# ESP12.net
KiCad netlist of a schematic drawn in Altium Designer
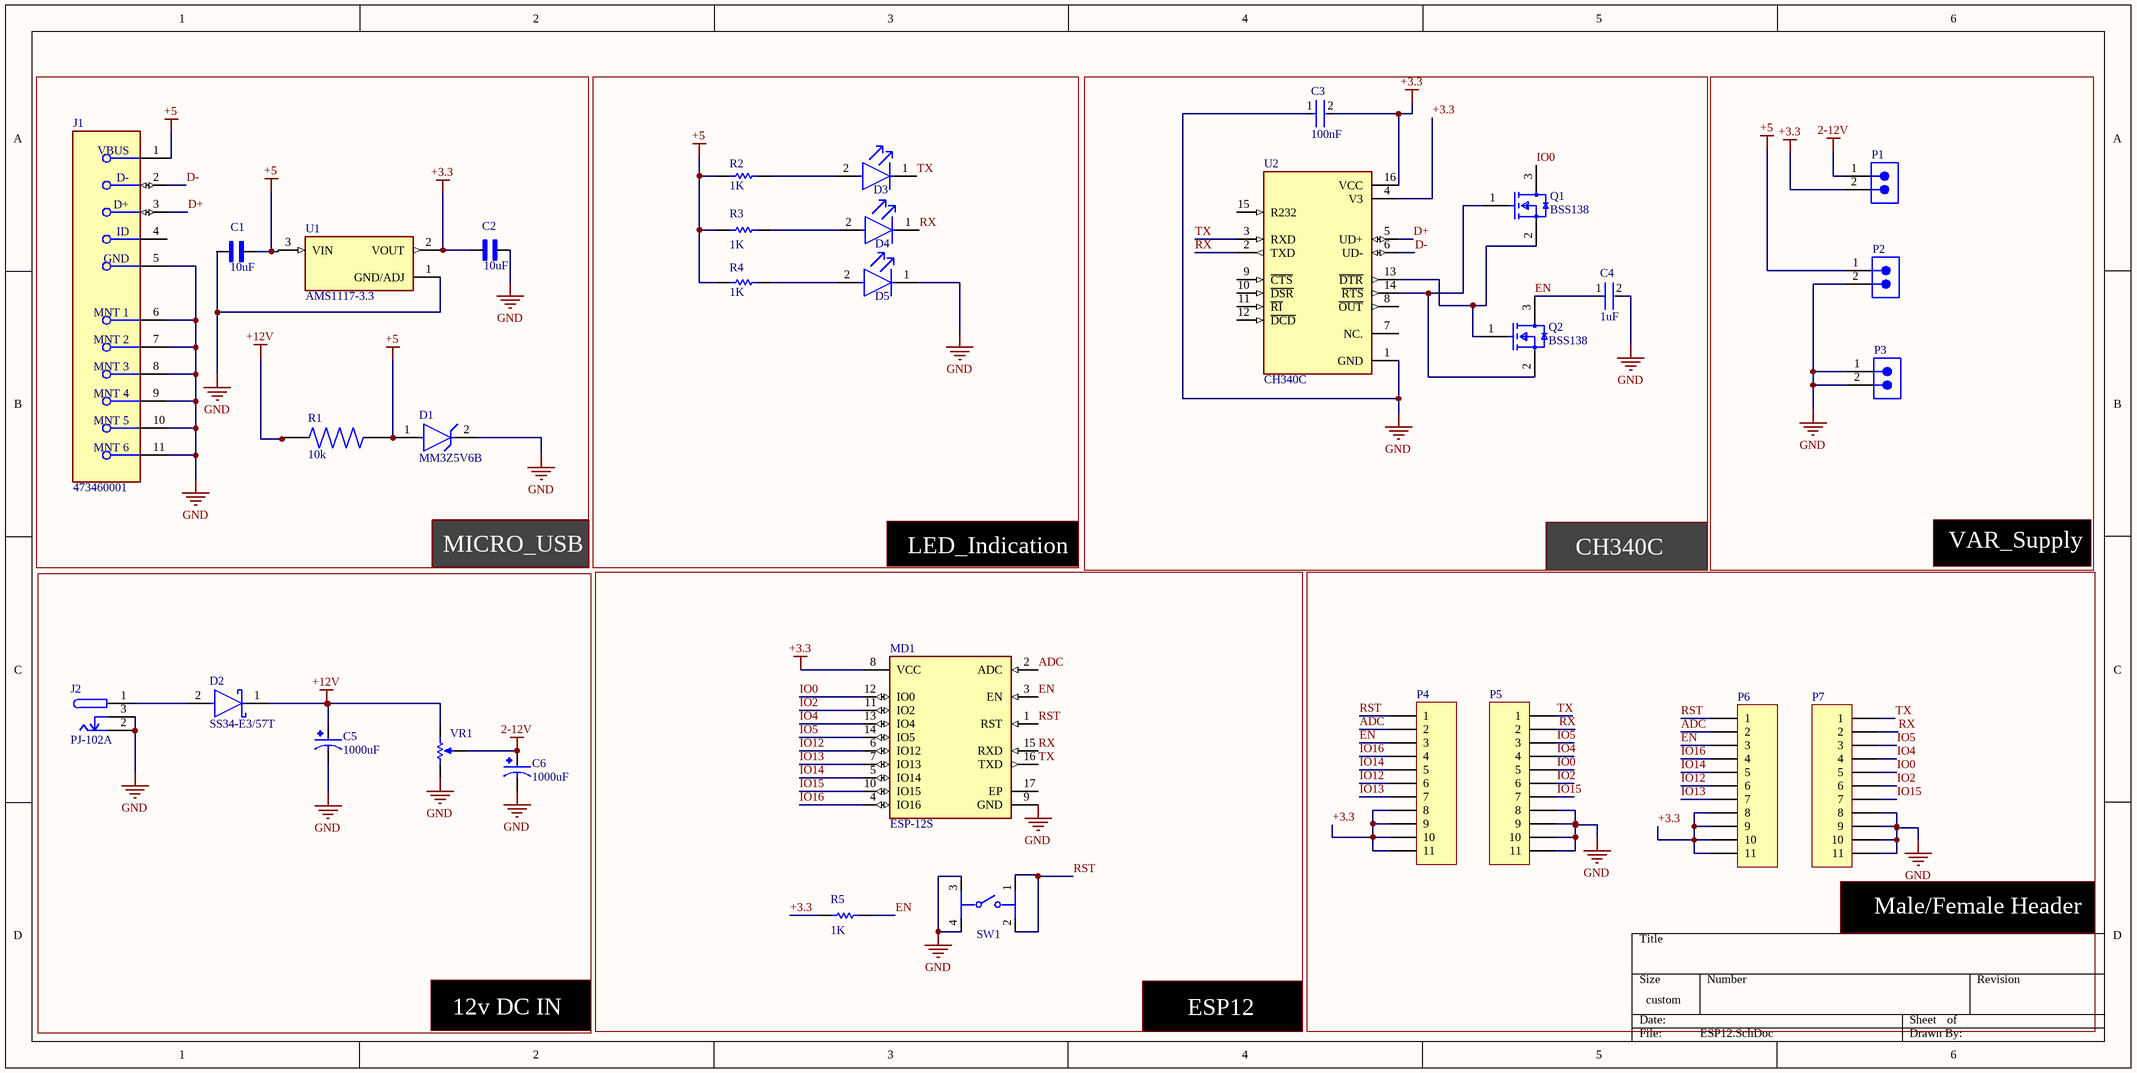
[diagram p0: ESP12.SchDoc]

(export (version "E")
  (design (tool "Eeschema 10.0.6"))
  (components
    (comp (ref "C1")
      (value "10uF")
      (footprint "CAPC2012X145N")
      (description "10 ÂµF Â±10% 25V Ceramic Capacitor X5R 0805 (2012 Metric)")
      (fields (field (name "MF") "Yageo") (field (name "MP") "CC0805KKX5R8BB106"))
      (libsource (lib "CC0805KKX5R8BB106") (part "CC0805KKX5R8BB106"))
    )
    (comp (ref "C2")
      (value "10uF")
      (footprint "CAPC2012X145N")
      (description "10 ÂµF Â±10% 25V Ceramic Capacitor X5R 0805 (2012 Metric)")
      (fields (field (name "MF") "Yageo") (field (name "MP") "CC0805KKX5R8BB106"))
      (libsource (lib "CC0805KKX5R8BB106") (part "CC0805KKX5R8BB106"))
    )
    (comp (ref "C3")
      (value "100nF")
      (footprint "FP-CC0805-0_85-MFG")
      (description "CAP CER 0.1UF 50V X7R 0805")
      (fields (field (name "TOLERANCE") "0.1") (field (name "MANUFACTURER PART NUMBER") "CC0805KRX7R9BB104"))
      (libsource (lib "Altium Content Vault") (part "11868f565c42a9108669ba33697ecf6"))
    )
    (comp (ref "C4")
      (value "1uF")
      (footprint "FP-CC0805-0_85-MFG")
      (description "CAP CER 1UF 16V X7R 0805")
      (fields
        (field (name "MANUFACTURER") "Yageo")
        (field (name "OCTOPART") "https://octopart.com/cc0805kkx7r7bb105-yageo-8376555")
      )
      (libsource (lib "Altium Content Vault") (part "11868f565c42a9108669ba33697ecf6"))
    )
    (comp (ref "C5")
      (value "1000uF")
      (footprint "CAPPRD500W60D1000H1600")
      (description "CAP ALUM 1000UF 20% 16V RADIAL")
      (fields (field (name "MF") "Panasonic") (field (name "MP") "EEU-FR1C102B"))
      (libsource (lib "EEUFR1C102B") (part "EEUFR1C102B"))
    )
    (comp (ref "C6")
      (value "1000uF")
      (footprint "CAPPRD500W60D1000H1600")
      (description "CAP ALUM 1000UF 20% 16V RADIAL")
      (fields (field (name "MF") "Panasonic") (field (name "MP") "EEU-FR1C102B"))
      (libsource (lib "EEUFR1C102B") (part "EEUFR1C102B"))
    )
    (comp (ref "D1")
      (value "MM3Z5V6B")
      (footprint "FP-MM3Z5V6B-MFG")
      (description "DIODE ZENER 5.6V 200MW SOD323F")
      (fields
        (field (name "MANUFACTURER") "ON Semiconductor")
        (field (name "OCTOPART") "https://octopart.com/mm3z5v6b-on+semiconductor-84329898")
      )
      (libsource (lib "Altium Content Vault") (part "3fba79ac723ca0a4e69928609483429"))
    )
    (comp (ref "D2")
      (value "SS34-E3/57T")
      (footprint "FP-95402-MFG")
      (description "DIODE SCHOTTKY 40V 3A DO214AB")
      (fields
        (field (name "MANUFACTURER") "Vishay")
        (field (name "OCTOPART") "https://octopart.com/ss34-e3%2F57t-vishay-39552907")
      )
      (libsource (lib "Altium Content Vault") (part "1d6ec82d83fb6aee721767c19dac4b9"))
    )
    (comp (ref "D3")
      (value "LTST-C190KRKT")
      (footprint "FP-LTST-C190KRKT-MFG")
      (description "LED RED CLEAR CHIP SMD")
      (libsource (lib "Altium Content Vault") (part "8706943c75ba83719d021d2fdc84c58"))
    )
    (comp (ref "D4")
      (value "LTST-C190KGKT")
      (footprint "FP-LTST-C190KGKT-MFG")
      (description "LED GREEN CLEAR CHIP SMD")
      (libsource (lib "Altium Content Vault") (part "8706943c75ba83719d021d2fdc84c58"))
    )
    (comp (ref "D5")
      (value "LTST-C190KRKT")
      (footprint "FP-LTST-C190KRKT-MFG")
      (description "LED RED CLEAR CHIP SMD")
      (libsource (lib "Altium Content Vault") (part "8706943c75ba83719d021d2fdc84c58"))
    )
    (comp (ref "J1")
      (value "473460001")
      (footprint "FP-473460001-MFG")
      (description "CONN RCPT USB2.0 MICRO B SMD R/A")
      (fields
        (field (name "OCTOPART") "https://octopart.com/47346-0001-molex-7164928")
        (field (name "MANUFACTURER") "Molex")
      )
      (libsource (lib "Altium Content Vault") (part "53ae1f1d9b557310b43ca686e5bb76a"))
    )
    (comp (ref "J2")
      (value "PJ-102A")
      (footprint "FP-PJ-102A-MFG")
      (description "PJ-102A 2.0 x 6.5 mm, 2.5 A, Horizontal, Through Hole, Tapered Pins, Dc Power Jack Connector")
      (libsource (lib "Altium Content Vault") (part "c639f672d24b5d70918fa8d934b95d1"))
    )
    (comp (ref "MD1")
      (value "ESP-12S")
      (footprint "FP-ESP-12S-MFG")
      (description "RX TXRX MOD WIFI PCB TRACE SMD")
      (libsource (lib "Altium Content Vault") (part "0473e498d6bc78f349d0f2898a8422c"))
    )
    (comp (ref "P1")
      (value "61300211121")
      (footprint "61300211121")
      (description "THT Vertical Pin Header WR-PHD, Pitch 2.54 mm, Single Row, 2 pins")
      (libsource (lib "Altium Content Vault") (part "Header_Male_1R_02P"))
    )
    (comp (ref "P2")
      (value "61300211121")
      (footprint "61300211121")
      (description "THT Vertical Pin Header WR-PHD, Pitch 2.54 mm, Single Row, 2 pins")
      (libsource (lib "Altium Content Vault") (part "Header_Male_1R_02P"))
    )
    (comp (ref "P3")
      (value "61300211121")
      (footprint "61300211121")
      (description "THT Vertical Pin Header WR-PHD, Pitch 2.54 mm, Single Row, 2 pins")
      (libsource (lib "Altium Content Vault") (part "Header_Male_1R_02P"))
    )
    (comp (ref "P4")
      (value "Header 11")
      (footprint "HDR1X11")
      (description "Header, 11-Pin")
      (fields (field (name "PUBLISHER") "Altium Limited"))
      (libsource (lib "") (part "Header 11_1"))
    )
    (comp (ref "P5")
      (value "Header 11")
      (footprint "HDR1X11")
      (description "Header, 11-Pin")
      (fields (field (name "PUBLISHER") "Altium Limited"))
      (libsource (lib "Miscellaneous Connectors") (part "Header 11"))
    )
    (comp (ref "P6")
      (value "Header 11")
      (footprint "HDR1X11")
      (description "Header, 11-Pin")
      (fields (field (name "PUBLISHER") "Altium Limited"))
      (libsource (lib "") (part "Header 11_1"))
    )
    (comp (ref "P7")
      (value "Header 11")
      (footprint "HDR1X11")
      (description "Header, 11-Pin")
      (fields (field (name "PUBLISHER") "Altium Limited"))
      (libsource (lib "Miscellaneous Connectors") (part "Header 11"))
    )
    (comp (ref "Q1")
      (value "BSS138")
      (footprint "FP-318-08-IPC_B")
      (description "MOSFET N-CH 50V 220MA SOT-23")
      (libsource (lib "Altium Content Vault") (part "3b9c635fedb024a5347a57b145af9cc"))
    )
    (comp (ref "Q2")
      (value "BSS138")
      (footprint "FP-318-08-IPC_B")
      (description "MOSFET N-CH 50V 220MA SOT-23")
      (libsource (lib "Altium Content Vault") (part "3b9c635fedb024a5347a57b145af9cc"))
    )
    (comp (ref "R1")
      (value "10k")
      (footprint "RESC2012X60N")
      (description "RESISTOR THICK FILM 5% 0.125W")
      (fields (field (name "MF") "{'manufacturer': u'YAGEO'}") (field (name "MP") "RC0805JR-0710KL"))
      (libsource (lib "RC0805JR-0710KL") (part "RC0805JR-0710KL"))
    )
    (comp (ref "R2")
      (value "1K")
      (footprint "RESC2013X60X35ML10T20")
      (description "Chip Resistor, 1 KOhm, +/- 1%, 125 mW, -55 to 155 degC, 0805 (2012 Metric), RoHS, Tape and Reel")
      (fields (field (name "TOLERANCE") "1%") (field (name "MANUFACTURER") "Yageo"))
      (libsource (lib "Altium Content Vault") (part "RES-2"))
    )
    (comp (ref "R3")
      (value "1K")
      (footprint "RESC2013X60X35ML10T20")
      (description "Chip Resistor, 1 KOhm, +/- 1%, 125 mW, -55 to 155 degC, 0805 (2012 Metric), RoHS, Tape and Reel")
      (fields (field (name "TOLERANCE") "1%") (field (name "MANUFACTURER") "Yageo"))
      (libsource (lib "Altium Content Vault") (part "RES-2"))
    )
    (comp (ref "R4")
      (value "1K")
      (footprint "RESC2013X60X35ML10T20")
      (description "Chip Resistor, 1 KOhm, +/- 1%, 125 mW, -55 to 155 degC, 0805 (2012 Metric), RoHS, Tape and Reel")
      (fields (field (name "TOLERANCE") "1%") (field (name "MANUFACTURER") "Yageo"))
      (libsource (lib "Altium Content Vault") (part "RES-2"))
    )
    (comp (ref "R5")
      (value "1K")
      (footprint "RESC2013X60X35ML10T20")
      (description "Chip Resistor, 1 KOhm, +/- 1%, 125 mW, -55 to 155 degC, 0805 (2012 Metric), RoHS, Tape and Reel")
      (fields (field (name "TOLERANCE") "1%") (field (name "MANUFACTURER") "Yageo"))
      (libsource (lib "Altium Content Vault") (part "RES-2"))
    )
    (comp (ref "SW1")
      (value "PTS645SM43SMTR92LFS")
      (footprint "PTS645SM43SMTR92LFS_MFG")
      (description "Switch Tactile N.O SPST Round Button Gull Wing 0.05A 12VDC 100000Cycle 1.57N SMD T/R")
      (libsource (lib "Altium Content Vault") (part "e4f2503661fe04264f50fb928c13ad2"))
    )
    (comp (ref "U1")
      (value "AMS1117-3.3")
      (footprint "SOT229P700X180-4N")
      (description "Sot223/Pkg 1-Amp 3.3-Volt Low Drop Out Voltage Regulatator")
      (fields (field (name "MF") "Advanced Monolithic Systems"))
      (libsource (lib "AMS1117-3.3") (part "AMS1117-3.3"))
    )
    (comp (ref "U2")
      (value "CH340C")
      (footprint "SOIC127P600X180-16N")
      (description "USB to serial chip CH340")
      (fields (field (name "MF") "WCH"))
      (libsource (lib "CH340C") (part "CH340C"))
    )
    (comp (ref "VR1")
      (value "3362P-1-103LF")
      (footprint "BOUR-3362P")
      (description "Square Trimpot(R) Trimming Potentiometer, 10 KOhm, 300 V, -55 to 125 degC, 3-Pin THD, RoHS, Tube")
      (fields (field (name "TOLERANCE") "1%"))
      (libsource (lib "Altium Content Vault") (part "RES-POT-3"))
    )
  )
  (nets
    (net (code "1") (name "+3.3") (class "Default")
      (node (ref "C2") (pin "1") (pinfunction "1_1") (pintype "passive"))
      (node (ref "C3") (pin "2") (pinfunction "2_2") (pintype "passive"))
      (node (ref "MD1") (pin "8") (pinfunction "VCC_8") (pintype "power_in"))
      (node (ref "P1") (pin "2") (pinfunction "2_2") (pintype "passive"))
      (node (ref "P4") (pin "10") (pinfunction "10_10") (pintype "passive"))
      (node (ref "P4") (pin "11") (pinfunction "11_11") (pintype "passive"))
      (node (ref "P4") (pin "8") (pinfunction "8_8") (pintype "passive"))
      (node (ref "P4") (pin "9") (pinfunction "9_9") (pintype "passive"))
      (node (ref "P6") (pin "10") (pinfunction "10_10") (pintype "passive"))
      (node (ref "P6") (pin "11") (pinfunction "11_11") (pintype "passive"))
      (node (ref "P6") (pin "8") (pinfunction "8_8") (pintype "passive"))
      (node (ref "P6") (pin "9") (pinfunction "9_9") (pintype "passive"))
      (node (ref "R5") (pin "1") (pinfunction "1_1") (pintype "passive"))
      (node (ref "U1") (pin "2") (pinfunction "VOUT_2") (pintype "output"))
      (node (ref "U2") (pin "16") (pinfunction "VCC_16") (pintype "power_in"))
      (node (ref "U2") (pin "4") (pinfunction "V3_4") (pintype "power_in"))
    )
    (net (code "2") (name "+5") (class "Default")
      (node (ref "C1") (pin "2") (pinfunction "2_2") (pintype "passive"))
      (node (ref "D1") (pin "1") (pinfunction "A_1") (pintype "passive"))
      (node (ref "J1") (pin "1") (pinfunction "VBUS_1") (pintype "power_in"))
      (node (ref "P2") (pin "1") (pinfunction "1_1") (pintype "passive"))
      (node (ref "R1") (pin "2") (pinfunction "2_2") (pintype "passive"))
      (node (ref "R2") (pin "1") (pinfunction "1_1") (pintype "passive"))
      (node (ref "R3") (pin "1") (pinfunction "1_1") (pintype "passive"))
      (node (ref "R4") (pin "1") (pinfunction "1_1") (pintype "passive"))
      (node (ref "U1") (pin "3") (pinfunction "VIN_3") (pintype "input"))
    )
    (net (code "3") (name "+12V") (class "Default")
      (node (ref "C5") (pin "P") (pinfunction "P_P") (pintype "passive"))
      (node (ref "D2") (pin "1") (pinfunction "C_1") (pintype "passive"))
      (node (ref "R1") (pin "1") (pinfunction "1_1") (pintype "passive"))
      (node (ref "VR1") (pin "3") (pinfunction "CW_3") (pintype "passive"))
    )
    (net (code "4") (name "/ADC") (class "Default")
      (node (ref "MD1") (pin "2") (pinfunction "ADC_2") (pintype "input"))
      (node (ref "P4") (pin "2") (pinfunction "2_2") (pintype "passive"))
      (node (ref "P6") (pin "2") (pinfunction "2_2") (pintype "passive"))
    )
    (net (code "5") (name "/D+") (class "Default")
      (node (ref "J1") (pin "3") (pinfunction "D+_3") (pintype "bidirectional"))
      (node (ref "U2") (pin "5") (pinfunction "UD+_5") (pintype "bidirectional"))
    )
    (net (code "6") (name "/D-") (class "Default")
      (node (ref "J1") (pin "2") (pinfunction "D-_2") (pintype "bidirectional"))
      (node (ref "U2") (pin "6") (pinfunction "UD-_6") (pintype "bidirectional"))
    )
    (net (code "7") (name "/EN") (class "Default")
      (node (ref "C4") (pin "1") (pinfunction "1_1") (pintype "passive"))
      (node (ref "MD1") (pin "3") (pinfunction "EN_3") (pintype "input"))
      (node (ref "P4") (pin "3") (pinfunction "3_3") (pintype "passive"))
      (node (ref "P6") (pin "3") (pinfunction "3_3") (pintype "passive"))
      (node (ref "Q2") (pin "3") (pinfunction "D_3") (pintype "passive"))
      (node (ref "R5") (pin "2") (pinfunction "2_2") (pintype "passive"))
    )
    (net (code "8") (name "/IO0") (class "Default")
      (node (ref "MD1") (pin "12") (pinfunction "IO0_12") (pintype "bidirectional"))
      (node (ref "P5") (pin "5") (pinfunction "5_5") (pintype "passive"))
      (node (ref "P7") (pin "5") (pinfunction "5_5") (pintype "passive"))
      (node (ref "Q1") (pin "3") (pinfunction "D_3") (pintype "passive"))
    )
    (net (code "9") (name "/IO2") (class "Default")
      (node (ref "MD1") (pin "11") (pinfunction "IO2_11") (pintype "bidirectional"))
      (node (ref "P5") (pin "6") (pinfunction "6_6") (pintype "passive"))
      (node (ref "P7") (pin "6") (pinfunction "6_6") (pintype "passive"))
    )
    (net (code "10") (name "/IO4") (class "Default")
      (node (ref "MD1") (pin "13") (pinfunction "IO4_13") (pintype "bidirectional"))
      (node (ref "P5") (pin "4") (pinfunction "4_4") (pintype "passive"))
      (node (ref "P7") (pin "4") (pinfunction "4_4") (pintype "passive"))
    )
    (net (code "11") (name "/IO5") (class "Default")
      (node (ref "MD1") (pin "14") (pinfunction "IO5_14") (pintype "bidirectional"))
      (node (ref "P5") (pin "3") (pinfunction "3_3") (pintype "passive"))
      (node (ref "P7") (pin "3") (pinfunction "3_3") (pintype "passive"))
    )
    (net (code "12") (name "/IO12") (class "Default")
      (node (ref "MD1") (pin "6") (pinfunction "IO12_6") (pintype "bidirectional"))
      (node (ref "P4") (pin "6") (pinfunction "6_6") (pintype "passive"))
      (node (ref "P6") (pin "6") (pinfunction "6_6") (pintype "passive"))
    )
    (net (code "13") (name "/IO13") (class "Default")
      (node (ref "MD1") (pin "7") (pinfunction "IO13_7") (pintype "bidirectional"))
      (node (ref "P4") (pin "7") (pinfunction "7_7") (pintype "passive"))
      (node (ref "P6") (pin "7") (pinfunction "7_7") (pintype "passive"))
    )
    (net (code "14") (name "/IO14") (class "Default")
      (node (ref "MD1") (pin "5") (pinfunction "IO14_5") (pintype "bidirectional"))
      (node (ref "P4") (pin "5") (pinfunction "5_5") (pintype "passive"))
      (node (ref "P6") (pin "5") (pinfunction "5_5") (pintype "passive"))
    )
    (net (code "15") (name "/IO15") (class "Default")
      (node (ref "MD1") (pin "10") (pinfunction "IO15_10") (pintype "bidirectional"))
      (node (ref "P5") (pin "7") (pinfunction "7_7") (pintype "passive"))
      (node (ref "P7") (pin "7") (pinfunction "7_7") (pintype "passive"))
    )
    (net (code "16") (name "/IO16") (class "Default")
      (node (ref "MD1") (pin "4") (pinfunction "IO16_4") (pintype "bidirectional"))
      (node (ref "P4") (pin "4") (pinfunction "4_4") (pintype "passive"))
      (node (ref "P6") (pin "4") (pinfunction "4_4") (pintype "passive"))
    )
    (net (code "17") (name "/RST") (class "Default")
      (node (ref "MD1") (pin "1") (pinfunction "RST_1") (pintype "input"))
      (node (ref "P4") (pin "1") (pinfunction "1_1") (pintype "passive"))
      (node (ref "P6") (pin "1") (pinfunction "1_1") (pintype "passive"))
      (node (ref "SW1") (pin "1") (pinfunction "1_1") (pintype "passive"))
      (node (ref "SW1") (pin "2") (pinfunction "2_2") (pintype "passive"))
    )
    (net (code "18") (name "/RX") (class "Default")
      (node (ref "D4") (pin "1") (pinfunction "C_1") (pintype "passive"))
      (node (ref "MD1") (pin "15") (pinfunction "RXD_15") (pintype "input"))
      (node (ref "P5") (pin "2") (pinfunction "2_2") (pintype "passive"))
      (node (ref "P7") (pin "2") (pinfunction "2_2") (pintype "passive"))
      (node (ref "U2") (pin "2") (pinfunction "TXD_2") (pintype "output"))
    )
    (net (code "19") (name "/TX") (class "Default")
      (node (ref "D3") (pin "1") (pinfunction "C_1") (pintype "passive"))
      (node (ref "MD1") (pin "16") (pinfunction "TXD_16") (pintype "output"))
      (node (ref "P5") (pin "1") (pinfunction "1_1") (pintype "passive"))
      (node (ref "P7") (pin "1") (pinfunction "1_1") (pintype "passive"))
      (node (ref "U2") (pin "3") (pinfunction "RXD_3") (pintype "input"))
    )
    (net (code "20") (name "2-12V") (class "Default")
      (node (ref "C6") (pin "P") (pinfunction "P_P") (pintype "passive"))
      (node (ref "P1") (pin "1") (pinfunction "1_1") (pintype "passive"))
      (node (ref "VR1") (pin "2") (pinfunction "S_2") (pintype "passive"))
    )
    (net (code "21") (name "GND") (class "Default")
      (node (ref "C1") (pin "1") (pinfunction "1_1") (pintype "passive"))
      (node (ref "C2") (pin "2") (pinfunction "2_2") (pintype "passive"))
      (node (ref "C3") (pin "1") (pinfunction "1_1") (pintype "passive"))
      (node (ref "C4") (pin "2") (pinfunction "2_2") (pintype "passive"))
      (node (ref "C5") (pin "N") (pinfunction "N_N") (pintype "passive"))
      (node (ref "C6") (pin "N") (pinfunction "N_N") (pintype "passive"))
      (node (ref "D1") (pin "2") (pinfunction "C_2") (pintype "passive"))
      (node (ref "D5") (pin "1") (pinfunction "C_1") (pintype "passive"))
      (node (ref "J1") (pin "10") (pinfunction "MNT_5_10") (pintype "passive"))
      (node (ref "J1") (pin "11") (pinfunction "MNT_6_11") (pintype "passive"))
      (node (ref "J1") (pin "5") (pinfunction "GND_5") (pintype "power_in"))
      (node (ref "J1") (pin "6") (pinfunction "MNT_1_6") (pintype "passive"))
      (node (ref "J1") (pin "7") (pinfunction "MNT_2_7") (pintype "passive"))
      (node (ref "J1") (pin "8") (pinfunction "MNT_3_8") (pintype "passive"))
      (node (ref "J1") (pin "9") (pinfunction "MNT_4_9") (pintype "passive"))
      (node (ref "J2") (pin "2") (pinfunction "2_2") (pintype "passive"))
      (node (ref "J2") (pin "3") (pinfunction "3_3") (pintype "passive"))
      (node (ref "MD1") (pin "9") (pinfunction "GND_9") (pintype "power_in"))
      (node (ref "P2") (pin "2") (pinfunction "2_2") (pintype "passive"))
      (node (ref "P3") (pin "1") (pinfunction "1_1") (pintype "passive"))
      (node (ref "P3") (pin "2") (pinfunction "2_2") (pintype "passive"))
      (node (ref "P5") (pin "10") (pinfunction "10_10") (pintype "passive"))
      (node (ref "P5") (pin "11") (pinfunction "11_11") (pintype "passive"))
      (node (ref "P5") (pin "8") (pinfunction "8_8") (pintype "passive"))
      (node (ref "P5") (pin "9") (pinfunction "9_9") (pintype "passive"))
      (node (ref "P7") (pin "10") (pinfunction "10_10") (pintype "passive"))
      (node (ref "P7") (pin "11") (pinfunction "11_11") (pintype "passive"))
      (node (ref "P7") (pin "8") (pinfunction "8_8") (pintype "passive"))
      (node (ref "P7") (pin "9") (pinfunction "9_9") (pintype "passive"))
      (node (ref "SW1") (pin "3") (pinfunction "3_3") (pintype "passive"))
      (node (ref "SW1") (pin "4") (pinfunction "4_4") (pintype "passive"))
      (node (ref "U1") (pin "1") (pinfunction "GND/ADJ_1") (pintype "power_in"))
      (node (ref "U2") (pin "1") (pinfunction "GND_1") (pintype "power_in"))
      (node (ref "VR1") (pin "1") (pinfunction "CCW_1") (pintype "passive"))
    )
    (net (code "22") (name "Net-(D2-A)") (class "Default")
      (node (ref "D2") (pin "2") (pinfunction "A_2") (pintype "passive"))
      (node (ref "J2") (pin "1") (pinfunction "1_1") (pintype "passive"))
    )
    (net (code "23") (name "Net-(D3-A)") (class "Default")
      (node (ref "D3") (pin "2") (pinfunction "A_2") (pintype "passive"))
      (node (ref "R2") (pin "2") (pinfunction "2_2") (pintype "passive"))
    )
    (net (code "24") (name "Net-(D4-A)") (class "Default")
      (node (ref "D4") (pin "2") (pinfunction "A_2") (pintype "passive"))
      (node (ref "R3") (pin "2") (pinfunction "2_2") (pintype "passive"))
    )
    (net (code "25") (name "Net-(D5-A)") (class "Default")
      (node (ref "D5") (pin "2") (pinfunction "A_2") (pintype "passive"))
      (node (ref "R4") (pin "2") (pinfunction "2_2") (pintype "passive"))
    )
    (net (code "26") (name "Net-(Q1-G)") (class "Default")
      (node (ref "Q1") (pin "1") (pinfunction "G_1") (pintype "passive"))
      (node (ref "Q2") (pin "2") (pinfunction "S_2") (pintype "passive"))
      (node (ref "U2") (pin "14") (pinfunction "~{RTS}_14") (pintype "output"))
    )
    (net (code "27") (name "Net-(Q1-S)") (class "Default")
      (node (ref "Q1") (pin "2") (pinfunction "S_2") (pintype "passive"))
      (node (ref "Q2") (pin "1") (pinfunction "G_1") (pintype "passive"))
      (node (ref "U2") (pin "13") (pinfunction "~{DTR}_13") (pintype "output"))
    )
    (net (code "28") (name "unconnected-(J1-ID-Pad4)") (class "Default")
      (node (ref "J1") (pin "4") (pinfunction "ID_4") (pintype "passive"))
    )
    (net (code "29") (name "unconnected-(MD1-EP-Pad17)") (class "Default")
      (node (ref "MD1") (pin "17") (pinfunction "EP_17") (pintype "power_in"))
    )
    (net (code "30") (name "unconnected-(U2-NC.-Pad7)") (class "Default")
      (node (ref "U2") (pin "7") (pinfunction "NC._7") (pintype "passive"))
    )
    (net (code "31") (name "unconnected-(U2-R232-Pad15)") (class "Default")
      (node (ref "U2") (pin "15") (pinfunction "R232_15") (pintype "input"))
    )
    (net (code "32") (name "unconnected-(U2-~{CTS}-Pad9)") (class "Default")
      (node (ref "U2") (pin "9") (pinfunction "~{CTS}_9") (pintype "input"))
    )
    (net (code "33") (name "unconnected-(U2-~{DCD}-Pad12)") (class "Default")
      (node (ref "U2") (pin "12") (pinfunction "~{DCD}_12") (pintype "input"))
    )
    (net (code "34") (name "unconnected-(U2-~{DSR}-Pad10)") (class "Default")
      (node (ref "U2") (pin "10") (pinfunction "~{DSR}_10") (pintype "input"))
    )
    (net (code "35") (name "unconnected-(U2-~{OUT}-Pad8)") (class "Default")
      (node (ref "U2") (pin "8") (pinfunction "~{OUT}_8") (pintype "output"))
    )
    (net (code "36") (name "unconnected-(U2-~{RI}-Pad11)") (class "Default")
      (node (ref "U2") (pin "11") (pinfunction "~{RI}_11") (pintype "input"))
    )
  )
)
